# HarvestRing.net
KiCad netlist of a schematic drawn in EAGLE
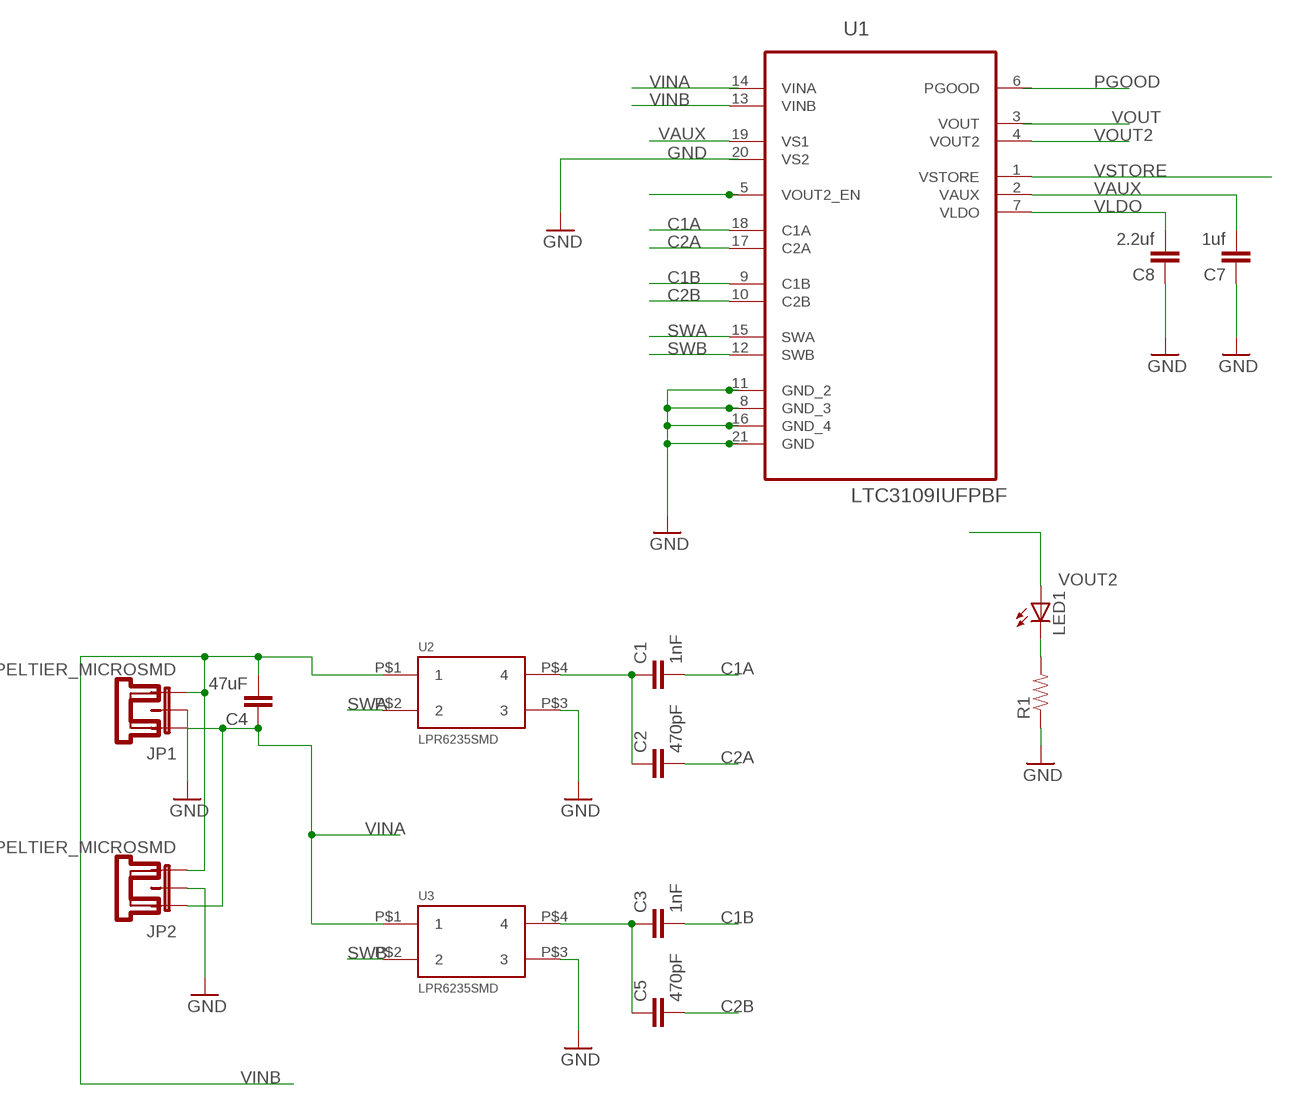
[diagram p0: schematic, sheet 1]

(export (version "E")
  (design (tool "Eeschema 10.0.6"))
  (components
    (comp (ref "C1")
      (value "1nF")
      (footprint "eagle-import:0603-CAP")
      (libsource (lib "eagle-import") (part "1NF/1000PF-50V-10%(0603)"))
    )
    (comp (ref "C2")
      (value "470pF")
      (footprint "eagle-import:0603-CAP")
      (libsource (lib "eagle-import") (part "22PF-50V-5%(0603)"))
    )
    (comp (ref "C3")
      (value "1nF")
      (footprint "eagle-import:0603-CAP")
      (libsource (lib "eagle-import") (part "1NF/1000PF-50V-10%(0603)"))
    )
    (comp (ref "C4")
      (value "47uF")
      (footprint "eagle-import:0603-CAP")
      (libsource (lib "eagle-import") (part "1NF/1000PF-50V-10%(0603)"))
    )
    (comp (ref "C5")
      (value "470pF")
      (footprint "eagle-import:0603-CAP")
      (libsource (lib "eagle-import") (part "22PF-50V-5%(0603)"))
    )
    (comp (ref "C7")
      (value "1uf")
      (footprint "eagle-import:0603-CAP")
      (libsource (lib "eagle-import") (part "1NF/1000PF-50V-10%(0603)"))
    )
    (comp (ref "C8")
      (value "2.2uf")
      (footprint "eagle-import:0603-CAP")
      (libsource (lib "eagle-import") (part "1NF/1000PF-50V-10%(0603)"))
    )
    (comp (ref "JP1")
      (value "PELTIER_MICROSMD")
      (footprint "eagle-import:HV56")
      (libsource (lib "eagle-import") (part "PELTIER_MICROSMD"))
    )
    (comp (ref "JP2")
      (value "PELTIER_MICROSMD")
      (footprint "eagle-import:HV56")
      (libsource (lib "eagle-import") (part "PELTIER_MICROSMD"))
    )
    (comp (ref "LED1")
      (value "LED1206")
      (footprint "eagle-import:LED-1206")
      (libsource (lib "eagle-import") (part "LED1206"))
    )
    (comp (ref "R1")
      (value "22K")
      (footprint "eagle-import:0603-RES")
      (libsource (lib "eagle-import") (part "22KOHM1/10W1%(0603)"))
    )
    (comp (ref "U1")
      (value "LTC3109IUFPBF")
      (footprint "eagle-import:QFN50P400X400X80-21N")
      (fields (field (name "MPN") "LTC3109IUF#PBF"))
      (libsource (lib "eagle-import") (part "LTC3109IUFPBF"))
    )
    (comp (ref "U2")
      (value "LPR6235SMD")
      (footprint "eagle-import:LPR6235")
      (libsource (lib "eagle-import") (part "LPR6235SMD"))
    )
    (comp (ref "U3")
      (value "LPR6235SMD")
      (footprint "eagle-import:LPR6235")
      (libsource (lib "eagle-import") (part "LPR6235SMD"))
    )
  )
  (nets
    (net (code "1") (name "/C1A") (class "Default")
      (node (ref "C1") (pin "2") (pinfunction "2_2") (pintype "passive"))
      (node (ref "U1") (pin "18") (pinfunction "C1A_18") (pintype "input"))
    )
    (net (code "2") (name "/C1B") (class "Default")
      (node (ref "C3") (pin "2") (pinfunction "2_2") (pintype "passive"))
      (node (ref "U1") (pin "9") (pinfunction "C1B_9") (pintype "input"))
    )
    (net (code "3") (name "/C2A") (class "Default")
      (node (ref "C2") (pin "2") (pinfunction "2_2") (pintype "passive"))
      (node (ref "U1") (pin "17") (pinfunction "C2A_17") (pintype "input"))
    )
    (net (code "4") (name "/C2B") (class "Default")
      (node (ref "C5") (pin "2") (pinfunction "2_2") (pintype "passive"))
      (node (ref "U1") (pin "10") (pinfunction "C2B_10") (pintype "input"))
    )
    (net (code "5") (name "/PGOOD") (class "Default")
      (node (ref "U1") (pin "5") (pinfunction "VOUT2_EN_5") (pintype "input"))
      (node (ref "U1") (pin "6") (pinfunction "PGOOD_6") (pintype "output"))
    )
    (net (code "6") (name "/SWA") (class "Default")
      (node (ref "U1") (pin "15") (pinfunction "SWA_15") (pintype "passive"))
      (node (ref "U2") (pin "P$2") (pinfunction "2_P$2") (pintype "bidirectional"))
    )
    (net (code "7") (name "/SWB") (class "Default")
      (node (ref "U1") (pin "12") (pinfunction "SWB_12") (pintype "passive"))
      (node (ref "U3") (pin "P$2") (pinfunction "2_P$2") (pintype "bidirectional"))
    )
    (net (code "8") (name "/VAUX") (class "Default")
      (node (ref "C7") (pin "2") (pinfunction "2_2") (pintype "passive"))
      (node (ref "U1") (pin "19") (pinfunction "VS1_19") (pintype "input"))
      (node (ref "U1") (pin "2") (pinfunction "VAUX_2") (pintype "output"))
    )
    (net (code "9") (name "/VINA") (class "Default")
      (node (ref "C4") (pin "1") (pinfunction "1_1") (pintype "passive"))
      (node (ref "JP1") (pin "1") (pinfunction "1_1") (pintype "output"))
      (node (ref "JP2") (pin "1") (pinfunction "1_1") (pintype "output"))
      (node (ref "U1") (pin "14") (pinfunction "VINA_14") (pintype "power_in"))
      (node (ref "U3") (pin "P$1") (pinfunction "1_P$1") (pintype "bidirectional"))
    )
    (net (code "10") (name "/VINB") (class "Default")
      (node (ref "C4") (pin "2") (pinfunction "2_2") (pintype "passive"))
      (node (ref "JP1") (pin "3") (pinfunction "3_3") (pintype "output"))
      (node (ref "JP2") (pin "3") (pinfunction "3_3") (pintype "output"))
      (node (ref "U1") (pin "13") (pinfunction "VINB_13") (pintype "power_in"))
      (node (ref "U2") (pin "P$1") (pinfunction "1_P$1") (pintype "bidirectional"))
    )
    (net (code "11") (name "/VLDO") (class "Default")
      (node (ref "C8") (pin "2") (pinfunction "2_2") (pintype "passive"))
      (node (ref "U1") (pin "7") (pinfunction "VLDO_7") (pintype "output"))
    )
    (net (code "12") (name "/VOUT") (class "Default")
      (node (ref "U1") (pin "3") (pinfunction "VOUT_3") (pintype "output"))
    )
    (net (code "13") (name "/VOUT2") (class "Default")
      (node (ref "LED1") (pin "A") (pinfunction "A_A") (pintype "passive"))
      (node (ref "U1") (pin "4") (pinfunction "VOUT2_4") (pintype "output"))
    )
    (net (code "14") (name "/VSTORE") (class "Default")
      (node (ref "U1") (pin "1") (pinfunction "VSTORE_1") (pintype "output"))
    )
    (net (code "15") (name "GND") (class "Default")
      (node (ref "C7") (pin "1") (pinfunction "1_1") (pintype "passive"))
      (node (ref "C8") (pin "1") (pinfunction "1_1") (pintype "passive"))
      (node (ref "JP1") (pin "2") (pinfunction "2_2") (pintype "passive"))
      (node (ref "JP2") (pin "2") (pinfunction "2_2") (pintype "passive"))
      (node (ref "R1") (pin "1") (pinfunction "1_1") (pintype "passive"))
      (node (ref "U1") (pin "11") (pinfunction "GND_2_11") (pintype "passive"))
      (node (ref "U1") (pin "16") (pinfunction "GND_4_16") (pintype "passive"))
      (node (ref "U1") (pin "20") (pinfunction "VS2_20") (pintype "input"))
      (node (ref "U1") (pin "21") (pinfunction "GND_21") (pintype "passive"))
      (node (ref "U1") (pin "8") (pinfunction "GND_3_8") (pintype "passive"))
      (node (ref "U2") (pin "P$3") (pinfunction "3_P$3") (pintype "bidirectional"))
      (node (ref "U3") (pin "P$3") (pinfunction "3_P$3") (pintype "bidirectional"))
    )
    (net (code "16") (name "Net-(LED1-PadC)") (class "Default")
      (node (ref "LED1") (pin "C") (pinfunction "C_C") (pintype "passive"))
      (node (ref "R1") (pin "2") (pinfunction "2_2") (pintype "passive"))
    )
    (net (code "17") (name "Net-(U2-4)") (class "Default")
      (node (ref "C1") (pin "1") (pinfunction "1_1") (pintype "passive"))
      (node (ref "C2") (pin "1") (pinfunction "1_1") (pintype "passive"))
      (node (ref "U2") (pin "P$4") (pinfunction "4_P$4") (pintype "bidirectional"))
    )
    (net (code "18") (name "Net-(U3-4)") (class "Default")
      (node (ref "C3") (pin "1") (pinfunction "1_1") (pintype "passive"))
      (node (ref "C5") (pin "1") (pinfunction "1_1") (pintype "passive"))
      (node (ref "U3") (pin "P$4") (pinfunction "4_P$4") (pintype "bidirectional"))
    )
  )
)
